# Fubarino_SDZ_v10.net
KiCad netlist of a schematic drawn in EAGLE
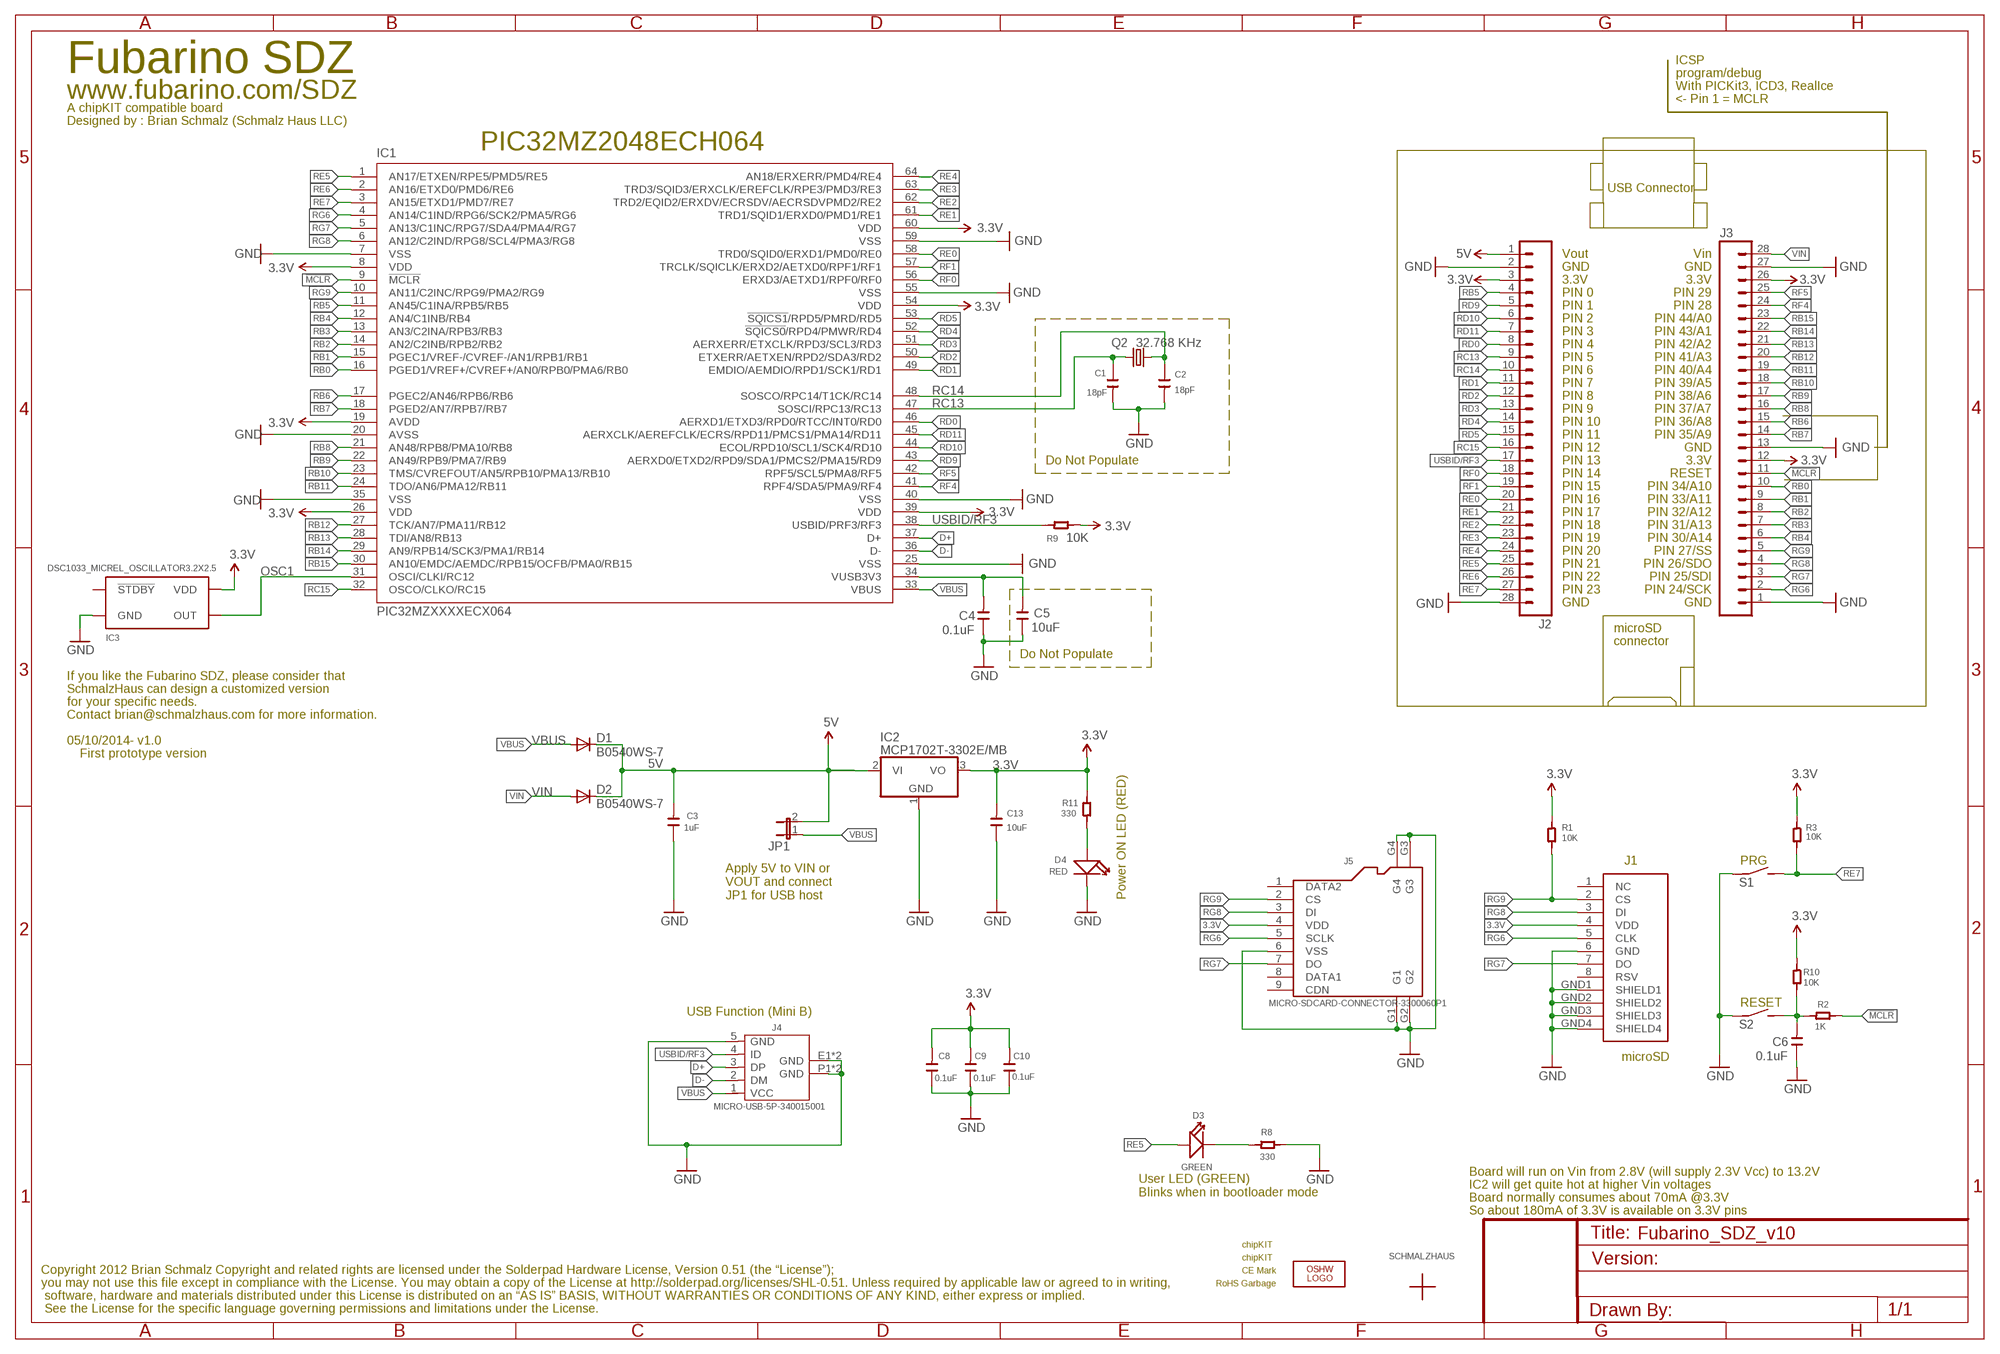
[diagram p0: schematic, sheet 1]

(export (version "E")
  (design (tool "Eeschema 10.0.6"))
  (components
    (comp (ref "C1")
      (value "18pF")
      (footprint "eagle-import:C0603")
      (libsource (lib "eagle-import") (part "C-0603"))
    )
    (comp (ref "C2")
      (value "18pF")
      (footprint "eagle-import:C0603")
      (libsource (lib "eagle-import") (part "C-0603"))
    )
    (comp (ref "C3")
      (value "1uF")
      (footprint "eagle-import:C0603")
      (libsource (lib "eagle-import") (part "C-0603"))
    )
    (comp (ref "C4")
      (value "0.1uF")
      (footprint "eagle-import:C0603")
      (libsource (lib "eagle-import") (part "C-0603"))
    )
    (comp (ref "C5")
      (value "10uF")
      (footprint "eagle-import:C0805")
      (libsource (lib "eagle-import") (part "C-0805"))
    )
    (comp (ref "C6")
      (value "0.1uF")
      (footprint "eagle-import:C0603")
      (libsource (lib "eagle-import") (part "C-0603"))
    )
    (comp (ref "C8")
      (value "0.1uF")
      (footprint "eagle-import:C0603")
      (libsource (lib "eagle-import") (part "C-0603"))
    )
    (comp (ref "C9")
      (value "0.1uF")
      (footprint "eagle-import:C0603")
      (libsource (lib "eagle-import") (part "C-0603"))
    )
    (comp (ref "C10")
      (value "0.1uF")
      (footprint "eagle-import:C0603")
      (libsource (lib "eagle-import") (part "C-0603"))
    )
    (comp (ref "C13")
      (value "10uF")
      (footprint "eagle-import:C0805")
      (libsource (lib "eagle-import") (part "C-0805"))
    )
    (comp (ref "D1")
      (value "B0540WS-7")
      (footprint "eagle-import:SOD-323")
      (libsource (lib "eagle-import") (part "DIODESOD"))
    )
    (comp (ref "D2")
      (value "B0540WS-7")
      (footprint "eagle-import:SOD-323")
      (libsource (lib "eagle-import") (part "DIODESOD"))
    )
    (comp (ref "D3")
      (value "GREEN")
      (footprint "eagle-import:LED0603")
      (libsource (lib "eagle-import") (part "LED"))
    )
    (comp (ref "D4")
      (value "RED")
      (footprint "eagle-import:LED0603")
      (libsource (lib "eagle-import") (part "LED"))
    )
    (comp (ref "IC1")
      (value "PIC32MZXXXXECX064")
      (footprint "eagle-import:TQFP64-10X10")
      (libsource (lib "eagle-import") (part "PIC32MZXXXXECX064"))
    )
    (comp (ref "IC2")
      (value "MCP1702T-3302E/MB")
      (footprint "eagle-import:SOT89")
      (libsource (lib "eagle-import") (part "MCP1703MB33"))
    )
    (comp (ref "IC3")
      (value "DSC1033_MICREL_OSCILLATOR3.2X2.5")
      (footprint "eagle-import:3.2X2.5_SILABS_OSC_DSC1033")
      (libsource (lib "eagle-import") (part "DSC1033_MICREL_OSCILLATOR3.2X2.5"))
    )
    (comp (ref "J1")
      (value "MICRO_SD_CARD_SOCKET")
      (footprint "eagle-import:SD-MMC_SOCKET-PP")
      (libsource (lib "eagle-import") (part "MICRO_SD_CARD_SOCKET"))
    )
    (comp (ref "J2")
      (value "M28USEPIN1")
      (footprint "eagle-import:1X28")
      (libsource (lib "eagle-import") (part "M28USEPIN1"))
    )
    (comp (ref "J3")
      (value "M28NOPIN1")
      (footprint "eagle-import:1X28_NO_PIN_1")
      (libsource (lib "eagle-import") (part "M28NOPIN1"))
    )
    (comp (ref "J4")
      (value "MICRO-USB-5P-340015001")
      (footprint "eagle-import:B-SMD-5P")
      (libsource (lib "eagle-import") (part "MICRO-USB-5P-340015001"))
    )
    (comp (ref "J5")
      (value "MICRO-SDCARD-CONNECTOR-3300060P1")
      (footprint "eagle-import:9P-SMD-W-RING")
      (libsource (lib "eagle-import") (part "MICRO-SDCARD-CONNECTOR-3300060P1"))
    )
    (comp (ref "JP1")
      (value "JUMPER-2SMD-NO")
      (footprint "eagle-import:SJ_2S-NO")
      (libsource (lib "eagle-import") (part "JUMPER-2SMD-NO"))
    )
    (comp (ref "LOGO1")
      (value "OSHW_LOGO_8MILX0070-NT")
      (footprint "eagle-import:OSHW_8X70_NOTEXT")
      (libsource (lib "eagle-import") (part "OSHW_LOGO_8MILX0070-NT"))
    )
    (comp (ref "Q2")
      (value "32.768 KHz")
      (footprint "eagle-import:TC26H")
      (libsource (lib "eagle-import") (part "CRYSTALTC26H"))
    )
    (comp (ref "R1")
      (value "10K")
      (footprint "eagle-import:R0603")
      (libsource (lib "eagle-import") (part "R-0603"))
    )
    (comp (ref "R2")
      (value "1K")
      (footprint "eagle-import:R0603")
      (libsource (lib "eagle-import") (part "R-0603"))
    )
    (comp (ref "R3")
      (value "10K")
      (footprint "eagle-import:R0603")
      (libsource (lib "eagle-import") (part "R-0603"))
    )
    (comp (ref "R8")
      (value "330")
      (footprint "eagle-import:R0603")
      (libsource (lib "eagle-import") (part "R-0603"))
    )
    (comp (ref "R9")
      (value "10K")
      (footprint "eagle-import:R0603")
      (libsource (lib "eagle-import") (part "R-0603"))
    )
    (comp (ref "R10")
      (value "10K")
      (footprint "eagle-import:R0603")
      (libsource (lib "eagle-import") (part "R-0603"))
    )
    (comp (ref "R11")
      (value "330")
      (footprint "eagle-import:R0603")
      (libsource (lib "eagle-import") (part "R-0603"))
    )
    (comp (ref "S1")
      (value "SWITCH")
      (footprint "eagle-import:SWITCH_KMR_SMT_TACT")
      (libsource (lib "eagle-import") (part "SWITCH"))
    )
    (comp (ref "S2")
      (value "SWITCH")
      (footprint "eagle-import:SWITCH_KMR_SMT_TACT")
      (libsource (lib "eagle-import") (part "SWITCH"))
    )
    (comp (ref "U$1")
      (value "SCHMALZHAUSSCHMALZHAUS_SMALL")
      (footprint "eagle-import:SCHMALZHAUS_SMALL")
      (libsource (lib "eagle-import") (part "SCHMALZHAUSSCHMALZHAUS_SMALL"))
    )
    (comp (ref "U$2")
      (value "CE_MARK5MM")
      (footprint "eagle-import:CE_5MM")
      (libsource (lib "eagle-import") (part "CE_MARK5MM"))
    )
    (comp (ref "U$3")
      (value "ROHS_GARBAGE")
      (footprint "eagle-import:ROHS_GARBAGE_5MM")
      (libsource (lib "eagle-import") (part "ROHS_GARBAGE"))
    )
    (comp (ref "U$4")
      (value "CHIPKIT2MM")
      (footprint "eagle-import:CHIPKIT_2MM")
      (libsource (lib "eagle-import") (part "CHIPKIT2MM"))
    )
    (comp (ref "U$5")
      (value "CHIPKIT2MM")
      (footprint "eagle-import:CHIPKIT_2MM")
      (libsource (lib "eagle-import") (part "CHIPKIT2MM"))
    )
  )
  (nets
    (net (code "1") (name "/OSC1") (class "Default")
      (node (ref "IC1") (pin "31") (pinfunction "OSCI/CLKI/RC12_31") (pintype "bidirectional"))
      (node (ref "IC3") (pin "P$3") (pinfunction "OUT_P$3") (pintype "output"))
    )
    (net (code "2") (name "/~{MCLR}") (class "Default")
      (node (ref "IC1") (pin "9") (pinfunction "~{MCLR}_9") (pintype "input"))
      (node (ref "J3") (pin "11") (pinfunction "11_11") (pintype "passive"))
      (node (ref "R2") (pin "2") (pinfunction "2_2") (pintype "bidirectional"))
    )
    (net (code "3") (name "3.3V") (class "Default")
      (node (ref "C10") (pin "1") (pinfunction "1_1") (pintype "bidirectional"))
      (node (ref "C13") (pin "1") (pinfunction "1_1") (pintype "bidirectional"))
      (node (ref "C8") (pin "1") (pinfunction "1_1") (pintype "bidirectional"))
      (node (ref "C9") (pin "1") (pinfunction "1_1") (pintype "bidirectional"))
      (node (ref "IC1") (pin "19") (pinfunction "AVDD_19") (pintype "power_in"))
      (node (ref "IC1") (pin "26") (pinfunction "VDD_26") (pintype "power_in"))
      (node (ref "IC1") (pin "39") (pinfunction "VDD_39") (pintype "power_in"))
      (node (ref "IC1") (pin "54") (pinfunction "VDD_54") (pintype "power_in"))
      (node (ref "IC1") (pin "60") (pinfunction "VDD_60") (pintype "power_in"))
      (node (ref "IC1") (pin "8") (pinfunction "VDD_8") (pintype "power_in"))
      (node (ref "IC2") (pin "3") (pinfunction "VO_3") (pintype "passive"))
      (node (ref "IC3") (pin "P$4") (pinfunction "VDD_P$4") (pintype "power_in"))
      (node (ref "J1") (pin "4") (pinfunction "VDD_4") (pintype "bidirectional"))
      (node (ref "J2") (pin "3") (pinfunction "3_3") (pintype "passive"))
      (node (ref "J3") (pin "12") (pinfunction "12_12") (pintype "passive"))
      (node (ref "J3") (pin "26") (pinfunction "26_26") (pintype "passive"))
      (node (ref "J5") (pin "4") (pinfunction "VDD_4") (pintype "bidirectional"))
      (node (ref "R1") (pin "1") (pinfunction "1_1") (pintype "bidirectional"))
      (node (ref "R10") (pin "1") (pinfunction "1_1") (pintype "bidirectional"))
      (node (ref "R11") (pin "2") (pinfunction "2_2") (pintype "bidirectional"))
      (node (ref "R3") (pin "1") (pinfunction "1_1") (pintype "bidirectional"))
      (node (ref "R9") (pin "2") (pinfunction "2_2") (pintype "bidirectional"))
    )
    (net (code "4") (name "5V") (class "Default")
      (node (ref "C3") (pin "1") (pinfunction "1_1") (pintype "bidirectional"))
      (node (ref "D1") (pin "1") (pinfunction "C_1") (pintype "passive"))
      (node (ref "D2") (pin "1") (pinfunction "C_1") (pintype "passive"))
      (node (ref "IC2") (pin "2") (pinfunction "VI_2") (pintype "input"))
      (node (ref "IC2") (pin "2@1") (pinfunction "VI1_2@1") (pintype "input"))
      (node (ref "J2") (pin "1") (pinfunction "1_1") (pintype "passive"))
      (node (ref "JP1") (pin "2") (pinfunction "2_2") (pintype "passive"))
    )
    (net (code "5") (name "D+") (class "Default")
      (node (ref "IC1") (pin "37") (pinfunction "D+_37") (pintype "bidirectional"))
      (node (ref "J4") (pin "3") (pinfunction "DP_3") (pintype "bidirectional"))
    )
    (net (code "6") (name "D-") (class "Default")
      (node (ref "IC1") (pin "36") (pinfunction "D-_36") (pintype "bidirectional"))
      (node (ref "J4") (pin "2") (pinfunction "DM_2") (pintype "bidirectional"))
    )
    (net (code "7") (name "GND") (class "Default")
      (node (ref "C1") (pin "1") (pinfunction "1_1") (pintype "bidirectional"))
      (node (ref "C10") (pin "2") (pinfunction "2_2") (pintype "bidirectional"))
      (node (ref "C13") (pin "2") (pinfunction "2_2") (pintype "bidirectional"))
      (node (ref "C2") (pin "1") (pinfunction "1_1") (pintype "bidirectional"))
      (node (ref "C3") (pin "2") (pinfunction "2_2") (pintype "bidirectional"))
      (node (ref "C4") (pin "2") (pinfunction "2_2") (pintype "bidirectional"))
      (node (ref "C5") (pin "2") (pinfunction "2_2") (pintype "bidirectional"))
      (node (ref "C6") (pin "2") (pinfunction "2_2") (pintype "bidirectional"))
      (node (ref "C8") (pin "2") (pinfunction "2_2") (pintype "bidirectional"))
      (node (ref "C9") (pin "2") (pinfunction "2_2") (pintype "bidirectional"))
      (node (ref "D4") (pin "-") (pinfunction "-_-") (pintype "passive"))
      (node (ref "IC1") (pin "20") (pinfunction "AVSS_20") (pintype "power_in"))
      (node (ref "IC1") (pin "25") (pinfunction "VSS_25") (pintype "power_in"))
      (node (ref "IC1") (pin "35") (pinfunction "VSS_35") (pintype "power_in"))
      (node (ref "IC1") (pin "40") (pinfunction "VSS_40") (pintype "power_in"))
      (node (ref "IC1") (pin "55") (pinfunction "VSS_55") (pintype "power_in"))
      (node (ref "IC1") (pin "59") (pinfunction "VSS_59") (pintype "power_in"))
      (node (ref "IC1") (pin "7") (pinfunction "VSS_7") (pintype "power_in"))
      (node (ref "IC2") (pin "1") (pinfunction "GND_1") (pintype "passive"))
      (node (ref "IC3") (pin "P$2") (pinfunction "GND_P$2") (pintype "power_in"))
      (node (ref "J1") (pin "6") (pinfunction "GND_6") (pintype "bidirectional"))
      (node (ref "J1") (pin "GND1") (pinfunction "SHIELD1_GND1") (pintype "bidirectional"))
      (node (ref "J1") (pin "GND2") (pinfunction "SHIELD2_GND2") (pintype "bidirectional"))
      (node (ref "J1") (pin "GND3") (pinfunction "SHIELD3_GND3") (pintype "bidirectional"))
      (node (ref "J1") (pin "GND4") (pinfunction "SHIELD4_GND4") (pintype "bidirectional"))
      (node (ref "J2") (pin "2") (pinfunction "2_2") (pintype "passive"))
      (node (ref "J2") (pin "28") (pinfunction "28_28") (pintype "passive"))
      (node (ref "J3") (pin "1") (pinfunction "1_1") (pintype "passive"))
      (node (ref "J3") (pin "13") (pinfunction "13_13") (pintype "passive"))
      (node (ref "J3") (pin "27") (pinfunction "27_27") (pintype "passive"))
      (node (ref "J4") (pin "5") (pinfunction "GND_5") (pintype "bidirectional"))
      (node (ref "J4") (pin "E1") (pinfunction "GND_E1") (pintype "bidirectional"))
      (node (ref "J4") (pin "E2") (pinfunction "GND_E2") (pintype "bidirectional"))
      (node (ref "J4") (pin "P1") (pinfunction "GND_P1") (pintype "bidirectional"))
      (node (ref "J4") (pin "P2") (pinfunction "GND_P2") (pintype "bidirectional"))
      (node (ref "J5") (pin "6") (pinfunction "VSS_6") (pintype "bidirectional"))
      (node (ref "J5") (pin "G1") (pinfunction "G1_G1") (pintype "bidirectional"))
      (node (ref "J5") (pin "G2") (pinfunction "G2_G2") (pintype "bidirectional"))
      (node (ref "J5") (pin "G3") (pinfunction "G3_G3") (pintype "bidirectional"))
      (node (ref "J5") (pin "G4") (pinfunction "G4_G4") (pintype "bidirectional"))
      (node (ref "R8") (pin "2") (pinfunction "2_2") (pintype "bidirectional"))
      (node (ref "S1") (pin "P$1") (pinfunction "1_P$1") (pintype "passive"))
      (node (ref "S1") (pin "P$2") (pinfunction "1_P$2") (pintype "passive"))
      (node (ref "S2") (pin "P$1") (pinfunction "1_P$1") (pintype "passive"))
      (node (ref "S2") (pin "P$2") (pinfunction "1_P$2") (pintype "passive"))
    )
    (net (code "8") (name "Net-(C6-Pad1)") (class "Default")
      (node (ref "C6") (pin "1") (pinfunction "1_1") (pintype "bidirectional"))
      (node (ref "R10") (pin "2") (pinfunction "2_2") (pintype "bidirectional"))
      (node (ref "R2") (pin "1") (pinfunction "1_1") (pintype "bidirectional"))
      (node (ref "S2") (pin "P$3") (pinfunction "2_P$3") (pintype "passive"))
      (node (ref "S2") (pin "P$4") (pinfunction "2_P$4") (pintype "passive"))
    )
    (net (code "9") (name "Net-(D3-Pad-)") (class "Default")
      (node (ref "D3") (pin "-") (pinfunction "-_-") (pintype "passive"))
      (node (ref "R8") (pin "1") (pinfunction "1_1") (pintype "bidirectional"))
    )
    (net (code "10") (name "Net-(D4-Pad+)") (class "Default")
      (node (ref "D4") (pin "+") (pinfunction "+_+") (pintype "passive"))
      (node (ref "R11") (pin "1") (pinfunction "1_1") (pintype "bidirectional"))
    )
    (net (code "11") (name "Net-(IC1-VUSB3V3)") (class "Default")
      (node (ref "C4") (pin "1") (pinfunction "1_1") (pintype "bidirectional"))
      (node (ref "C5") (pin "1") (pinfunction "1_1") (pintype "bidirectional"))
      (node (ref "IC1") (pin "34") (pinfunction "VUSB3V3_34") (pintype "power_in"))
    )
    (net (code "12") (name "RB0") (class "Default")
      (node (ref "IC1") (pin "16") (pinfunction "PGED1/VREF+/CVREF+/AN0/RPB0/PMA6/RB0_16") (pintype "bidirectional"))
      (node (ref "J3") (pin "10") (pinfunction "10_10") (pintype "passive"))
    )
    (net (code "13") (name "RB1") (class "Default")
      (node (ref "IC1") (pin "15") (pinfunction "PGEC1/VREF-/CVREF-/AN1/RPB1/RB1_15") (pintype "bidirectional"))
      (node (ref "J3") (pin "9") (pinfunction "9_9") (pintype "passive"))
    )
    (net (code "14") (name "RB2") (class "Default")
      (node (ref "IC1") (pin "14") (pinfunction "AN2/C2INB/RPB2/RB2_14") (pintype "bidirectional"))
      (node (ref "J3") (pin "8") (pinfunction "8_8") (pintype "passive"))
    )
    (net (code "15") (name "RB3") (class "Default")
      (node (ref "IC1") (pin "13") (pinfunction "AN3/C2INA/RPB3/RB3_13") (pintype "bidirectional"))
      (node (ref "J3") (pin "7") (pinfunction "7_7") (pintype "passive"))
    )
    (net (code "16") (name "RB4") (class "Default")
      (node (ref "IC1") (pin "12") (pinfunction "AN4/C1INB/RB4_12") (pintype "bidirectional"))
      (node (ref "J3") (pin "6") (pinfunction "6_6") (pintype "passive"))
    )
    (net (code "17") (name "RB5") (class "Default")
      (node (ref "IC1") (pin "11") (pinfunction "AN45/C1INA/RPB5/RB5_11") (pintype "bidirectional"))
      (node (ref "J2") (pin "4") (pinfunction "4_4") (pintype "passive"))
    )
    (net (code "18") (name "RB6") (class "Default")
      (node (ref "IC1") (pin "17") (pinfunction "PGEC2/AN46/RPB6/RB6_17") (pintype "bidirectional"))
      (node (ref "J3") (pin "15") (pinfunction "15_15") (pintype "passive"))
    )
    (net (code "19") (name "RB7") (class "Default")
      (node (ref "IC1") (pin "18") (pinfunction "PGED2/AN7/RPB7/RB7_18") (pintype "bidirectional"))
      (node (ref "J3") (pin "14") (pinfunction "14_14") (pintype "passive"))
    )
    (net (code "20") (name "RB8") (class "Default")
      (node (ref "IC1") (pin "21") (pinfunction "AN48/RPB8/PMA10/RB8_21") (pintype "bidirectional"))
      (node (ref "J3") (pin "16") (pinfunction "16_16") (pintype "passive"))
    )
    (net (code "21") (name "RB9") (class "Default")
      (node (ref "IC1") (pin "22") (pinfunction "AN49/RPB9/PMA7/RB9_22") (pintype "bidirectional"))
      (node (ref "J3") (pin "17") (pinfunction "17_17") (pintype "passive"))
    )
    (net (code "22") (name "RB10") (class "Default")
      (node (ref "IC1") (pin "23") (pinfunction "TMS/CVREFOUT/AN5/RPB10/PMA13/RB10_23") (pintype "bidirectional"))
      (node (ref "J3") (pin "18") (pinfunction "18_18") (pintype "passive"))
    )
    (net (code "23") (name "RB11") (class "Default")
      (node (ref "IC1") (pin "24") (pinfunction "TDO/AN6/PMA12/RB11_24") (pintype "bidirectional"))
      (node (ref "J3") (pin "19") (pinfunction "19_19") (pintype "passive"))
    )
    (net (code "24") (name "RB12") (class "Default")
      (node (ref "IC1") (pin "27") (pinfunction "TCK/AN7/PMA11/RB12_27") (pintype "bidirectional"))
      (node (ref "J3") (pin "20") (pinfunction "20_20") (pintype "passive"))
    )
    (net (code "25") (name "RB13") (class "Default")
      (node (ref "IC1") (pin "28") (pinfunction "TDI/AN8/RB13_28") (pintype "bidirectional"))
      (node (ref "J3") (pin "21") (pinfunction "21_21") (pintype "passive"))
    )
    (net (code "26") (name "RB14") (class "Default")
      (node (ref "IC1") (pin "29") (pinfunction "AN9/RPB14/SCK3/PMA1/RB14_29") (pintype "bidirectional"))
      (node (ref "J3") (pin "22") (pinfunction "22_22") (pintype "passive"))
    )
    (net (code "27") (name "RB15") (class "Default")
      (node (ref "IC1") (pin "30") (pinfunction "AN10/EMDC/AEMDC/RPB15/OCFB/PMA0/RB15_30") (pintype "bidirectional"))
      (node (ref "J3") (pin "23") (pinfunction "23_23") (pintype "passive"))
    )
    (net (code "28") (name "RC13") (class "Default")
      (node (ref "C1") (pin "2") (pinfunction "2_2") (pintype "bidirectional"))
      (node (ref "IC1") (pin "47") (pinfunction "SOSCI/RPC13/RC13_47") (pintype "bidirectional"))
      (node (ref "J2") (pin "9") (pinfunction "9_9") (pintype "passive"))
      (node (ref "Q2") (pin "1") (pinfunction "1_1") (pintype "passive"))
    )
    (net (code "29") (name "RC14") (class "Default")
      (node (ref "C2") (pin "2") (pinfunction "2_2") (pintype "bidirectional"))
      (node (ref "IC1") (pin "48") (pinfunction "SOSCO/RPC14/T1CK/RC14_48") (pintype "bidirectional"))
      (node (ref "J2") (pin "10") (pinfunction "10_10") (pintype "passive"))
      (node (ref "Q2") (pin "2") (pinfunction "2_2") (pintype "passive"))
    )
    (net (code "30") (name "RC15") (class "Default")
      (node (ref "IC1") (pin "32") (pinfunction "OSCO/CLKO/RC15_32") (pintype "bidirectional"))
      (node (ref "J2") (pin "16") (pinfunction "16_16") (pintype "passive"))
    )
    (net (code "31") (name "RD0") (class "Default")
      (node (ref "IC1") (pin "46") (pinfunction "AERXD1/ETXD3/RPD0/RTCC/INT0/RD0_46") (pintype "bidirectional"))
      (node (ref "J2") (pin "8") (pinfunction "8_8") (pintype "passive"))
    )
    (net (code "32") (name "RD1") (class "Default")
      (node (ref "IC1") (pin "49") (pinfunction "EMDIO/AEMDIO/RPD1/SCK1/RD1_49") (pintype "bidirectional"))
      (node (ref "J2") (pin "11") (pinfunction "11_11") (pintype "passive"))
    )
    (net (code "33") (name "RD2") (class "Default")
      (node (ref "IC1") (pin "50") (pinfunction "ETXERR/AETXEN/RPD2/SDA3/RD2_50") (pintype "bidirectional"))
      (node (ref "J2") (pin "12") (pinfunction "12_12") (pintype "passive"))
    )
    (net (code "34") (name "RD3") (class "Default")
      (node (ref "IC1") (pin "51") (pinfunction "AERXERR/ETXCLK/RPD3/SCL3/RD3_51") (pintype "bidirectional"))
      (node (ref "J2") (pin "13") (pinfunction "13_13") (pintype "passive"))
    )
    (net (code "35") (name "RD4") (class "Default")
      (node (ref "IC1") (pin "52") (pinfunction "~{SQICS0}/RPD4/PMWR/RD4_52") (pintype "bidirectional"))
      (node (ref "J2") (pin "14") (pinfunction "14_14") (pintype "passive"))
    )
    (net (code "36") (name "RD5") (class "Default")
      (node (ref "IC1") (pin "53") (pinfunction "~{SQICS1}/RPD5/PMRD/RD5_53") (pintype "bidirectional"))
      (node (ref "J2") (pin "15") (pinfunction "15_15") (pintype "passive"))
    )
    (net (code "37") (name "RD9") (class "Default")
      (node (ref "IC1") (pin "43") (pinfunction "AERXD0/ETXD2/RPD9/SDA1/PMCS2/PMA15/RD9_43") (pintype "bidirectional"))
      (node (ref "J2") (pin "5") (pinfunction "5_5") (pintype "passive"))
    )
    (net (code "38") (name "RD10") (class "Default")
      (node (ref "IC1") (pin "44") (pinfunction "ECOL/RPD10/SCL1/SCK4/RD10_44") (pintype "bidirectional"))
      (node (ref "J2") (pin "6") (pinfunction "6_6") (pintype "passive"))
    )
    (net (code "39") (name "RD11") (class "Default")
      (node (ref "IC1") (pin "45") (pinfunction "AERXCLK/AEREFCLK/ECRS/RPD11/PMCS1/PMA14/RD11_45") (pintype "bidirectional"))
      (node (ref "J2") (pin "7") (pinfunction "7_7") (pintype "passive"))
    )
    (net (code "40") (name "RE0") (class "Default")
      (node (ref "IC1") (pin "58") (pinfunction "TRD0/SQID0/ERXD1/PMD0/RE0_58") (pintype "bidirectional"))
      (node (ref "J2") (pin "20") (pinfunction "20_20") (pintype "passive"))
    )
    (net (code "41") (name "RE1") (class "Default")
      (node (ref "IC1") (pin "61") (pinfunction "TRD1/SQID1/ERXD0/PMD1/RE1_61") (pintype "bidirectional"))
      (node (ref "J2") (pin "21") (pinfunction "21_21") (pintype "passive"))
    )
    (net (code "42") (name "RE2") (class "Default")
      (node (ref "IC1") (pin "62") (pinfunction "TRD2/EQID2/ERXDV/ECRSDV/AECRSDVPMD2/RE2_62") (pintype "bidirectional"))
      (node (ref "J2") (pin "22") (pinfunction "22_22") (pintype "passive"))
    )
    (net (code "43") (name "RE3") (class "Default")
      (node (ref "IC1") (pin "63") (pinfunction "TRD3/SQID3/ERXCLK/EREFCLK/RPE3/PMD3/RE3_63") (pintype "bidirectional"))
      (node (ref "J2") (pin "23") (pinfunction "23_23") (pintype "passive"))
    )
    (net (code "44") (name "RE4") (class "Default")
      (node (ref "IC1") (pin "64") (pinfunction "AN18/ERXERR/PMD4/RE4_64") (pintype "bidirectional"))
      (node (ref "J2") (pin "24") (pinfunction "24_24") (pintype "passive"))
    )
    (net (code "45") (name "RE5") (class "Default")
      (node (ref "D3") (pin "+") (pinfunction "+_+") (pintype "passive"))
      (node (ref "IC1") (pin "1") (pinfunction "AN17/ETXEN/RPE5/PMD5/RE5_1") (pintype "bidirectional"))
      (node (ref "J2") (pin "25") (pinfunction "25_25") (pintype "passive"))
    )
    (net (code "46") (name "RE6") (class "Default")
      (node (ref "IC1") (pin "2") (pinfunction "AN16/ETXD0/PMD6/RE6_2") (pintype "bidirectional"))
      (node (ref "J2") (pin "26") (pinfunction "26_26") (pintype "passive"))
    )
    (net (code "47") (name "RE7") (class "Default")
      (node (ref "IC1") (pin "3") (pinfunction "AN15/ETXD1/PMD7/RE7_3") (pintype "bidirectional"))
      (node (ref "J2") (pin "27") (pinfunction "27_27") (pintype "passive"))
      (node (ref "R3") (pin "2") (pinfunction "2_2") (pintype "bidirectional"))
      (node (ref "S1") (pin "P$3") (pinfunction "2_P$3") (pintype "passive"))
      (node (ref "S1") (pin "P$4") (pinfunction "2_P$4") (pintype "passive"))
    )
    (net (code "48") (name "RF0") (class "Default")
      (node (ref "IC1") (pin "56") (pinfunction "ERXD3/AETXD1/RPF0/RF0_56") (pintype "bidirectional"))
      (node (ref "J2") (pin "18") (pinfunction "18_18") (pintype "passive"))
    )
    (net (code "49") (name "RF1") (class "Default")
      (node (ref "IC1") (pin "57") (pinfunction "TRCLK/SQICLK/ERXD2/AETXD0/RPF1/RF1_57") (pintype "bidirectional"))
      (node (ref "J2") (pin "19") (pinfunction "19_19") (pintype "passive"))
    )
    (net (code "50") (name "RF4") (class "Default")
      (node (ref "IC1") (pin "41") (pinfunction "RPF4/SDA5/PMA9/RF4_41") (pintype "bidirectional"))
      (node (ref "J3") (pin "24") (pinfunction "24_24") (pintype "passive"))
    )
    (net (code "51") (name "RF5") (class "Default")
      (node (ref "IC1") (pin "42") (pinfunction "RPF5/SCL5/PMA8/RF5_42") (pintype "bidirectional"))
      (node (ref "J3") (pin "25") (pinfunction "25_25") (pintype "passive"))
    )
    (net (code "52") (name "RG6") (class "Default")
      (node (ref "IC1") (pin "4") (pinfunction "AN14/C1IND/RPG6/SCK2/PMA5/RG6_4") (pintype "bidirectional"))
      (node (ref "J1") (pin "5") (pinfunction "CLK_5") (pintype "bidirectional"))
      (node (ref "J3") (pin "2") (pinfunction "2_2") (pintype "passive"))
      (node (ref "J5") (pin "5") (pinfunction "SCLK_5") (pintype "bidirectional"))
    )
    (net (code "53") (name "RG7") (class "Default")
      (node (ref "IC1") (pin "5") (pinfunction "AN13/C1INC/RPG7/SDA4/PMA4/RG7_5") (pintype "bidirectional"))
      (node (ref "J1") (pin "7") (pinfunction "DO_7") (pintype "bidirectional"))
      (node (ref "J3") (pin "3") (pinfunction "3_3") (pintype "passive"))
      (node (ref "J5") (pin "7") (pinfunction "DO_7") (pintype "bidirectional"))
    )
    (net (code "54") (name "RG8") (class "Default")
      (node (ref "IC1") (pin "6") (pinfunction "AN12/C2IND/RPG8/SCL4/PMA3/RG8_6") (pintype "bidirectional"))
      (node (ref "J1") (pin "3") (pinfunction "DI_3") (pintype "bidirectional"))
      (node (ref "J3") (pin "4") (pinfunction "4_4") (pintype "passive"))
      (node (ref "J5") (pin "3") (pinfunction "DI_3") (pintype "bidirectional"))
    )
    (net (code "55") (name "RG9") (class "Default")
      (node (ref "IC1") (pin "10") (pinfunction "AN11/C2INC/RPG9/PMA2/RG9_10") (pintype "bidirectional"))
      (node (ref "J1") (pin "2") (pinfunction "CS_2") (pintype "bidirectional"))
      (node (ref "J3") (pin "5") (pinfunction "5_5") (pintype "passive"))
      (node (ref "J5") (pin "2") (pinfunction "CS_2") (pintype "bidirectional"))
      (node (ref "R1") (pin "2") (pinfunction "2_2") (pintype "bidirectional"))
    )
    (net (code "56") (name "USBID{slash}RF3") (class "Default")
      (node (ref "IC1") (pin "38") (pinfunction "USBID/PRF3/RF3_38") (pintype "bidirectional"))
      (node (ref "J2") (pin "17") (pinfunction "17_17") (pintype "passive"))
      (node (ref "J4") (pin "4") (pinfunction "ID_4") (pintype "bidirectional"))
      (node (ref "R9") (pin "1") (pinfunction "1_1") (pintype "bidirectional"))
    )
    (net (code "57") (name "VBUS") (class "Default")
      (node (ref "D1") (pin "2") (pinfunction "A_2") (pintype "passive"))
      (node (ref "IC1") (pin "33") (pinfunction "VBUS_33") (pintype "input"))
      (node (ref "J4") (pin "1") (pinfunction "VCC_1") (pintype "bidirectional"))
      (node (ref "JP1") (pin "1") (pinfunction "1_1") (pintype "passive"))
    )
    (net (code "58") (name "VIN") (class "Default")
      (node (ref "D2") (pin "2") (pinfunction "A_2") (pintype "passive"))
      (node (ref "J3") (pin "28") (pinfunction "28_28") (pintype "passive"))
    )
    (net (code "59") (name "unconnected-(IC3-~{STDBY}-PadP$1)") (class "Default")
      (node (ref "IC3") (pin "P$1") (pinfunction "~{STDBY}_P$1") (pintype "input"))
    )
    (net (code "60") (name "unconnected-(J1-NC-Pad1)") (class "Default")
      (node (ref "J1") (pin "1") (pinfunction "NC_1") (pintype "bidirectional"))
    )
    (net (code "61") (name "unconnected-(J1-RSV-Pad8)") (class "Default")
      (node (ref "J1") (pin "8") (pinfunction "RSV_8") (pintype "bidirectional"))
    )
    (net (code "62") (name "unconnected-(J5-CDN-Pad9)") (class "Default")
      (node (ref "J5") (pin "9") (pinfunction "CDN_9") (pintype "bidirectional"))
    )
    (net (code "63") (name "unconnected-(J5-DATA1-Pad8)") (class "Default")
      (node (ref "J5") (pin "8") (pinfunction "DATA1_8") (pintype "bidirectional"))
    )
    (net (code "64") (name "unconnected-(J5-DATA2-Pad1)") (class "Default")
      (node (ref "J5") (pin "1") (pinfunction "DATA2_1") (pintype "bidirectional"))
    )
  )
)
